# yack.net
KiCad netlist of a schematic drawn in EAGLE
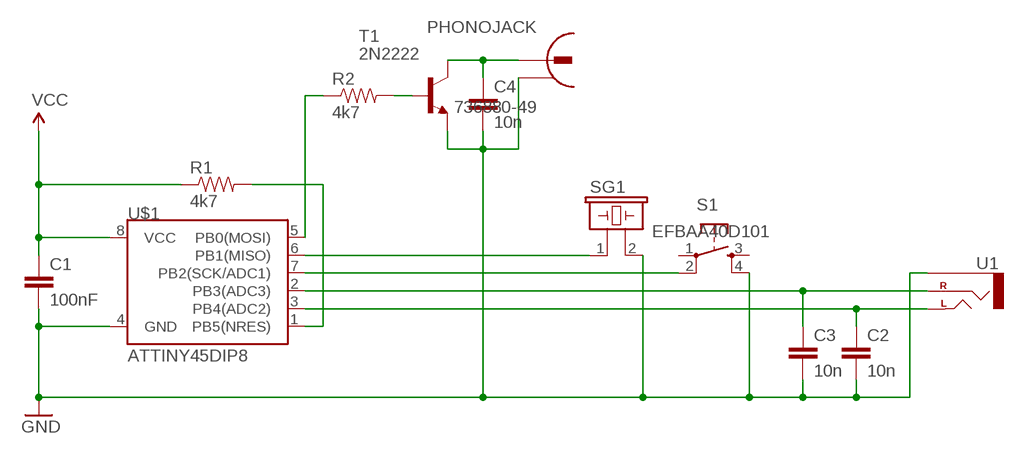
[diagram p0: schematic, sheet 1]

(export (version "E")
  (design (tool "Eeschema 10.0.6"))
  (components
    (comp (ref "C1")
      (value "100nF")
      (footprint "eagle-import:CAP-PTH-SMALL-KIT")
      (libsource (lib "eagle-import") (part "CAPKIT"))
    )
    (comp (ref "C2")
      (value "10n")
      (footprint "eagle-import:CAP-PTH-SMALL-KIT")
      (libsource (lib "eagle-import") (part "CAPKIT"))
    )
    (comp (ref "C3")
      (value "10n")
      (footprint "eagle-import:CAP-PTH-SMALL-KIT")
      (libsource (lib "eagle-import") (part "CAPKIT"))
    )
    (comp (ref "C4")
      (value "10n")
      (footprint "eagle-import:CAP-PTH-SMALL-KIT")
      (libsource (lib "eagle-import") (part "CAPKIT"))
    )
    (comp (ref "PHONOJACK")
      (value "736880-49")
      (footprint "eagle-import:736880-49")
      (libsource (lib "eagle-import") (part "736880-49"))
    )
    (comp (ref "R1")
      (value "4k7")
      (footprint "eagle-import:AXIAL-0.3-KIT")
      (libsource (lib "eagle-import") (part "RESISTORKIT"))
    )
    (comp (ref "R2")
      (value "4k7")
      (footprint "eagle-import:AXIAL-0.3-KIT")
      (libsource (lib "eagle-import") (part "RESISTORKIT"))
    )
    (comp (ref "S1")
      (value "TAC_SWITCHPTH")
      (footprint "eagle-import:TACTILE-PTH")
      (libsource (lib "eagle-import") (part "TAC_SWITCHPTH"))
    )
    (comp (ref "SG1")
      (value "EFBAA40D101")
      (footprint "eagle-import:EFBAA40D101")
      (libsource (lib "eagle-import") (part "EFB?AA40D101"))
    )
    (comp (ref "T1")
      (value "2N2222")
      (footprint "eagle-import:TO92-EBC-OVAL")
      (libsource (lib "eagle-import") (part "2N2222"))
    )
    (comp (ref "U$1")
      (value "ATTINY45DIP8")
      (footprint "eagle-import:DIP08")
      (libsource (lib "eagle-import") (part "ATTINY45DIP8"))
    )
    (comp (ref "U1")
      (value "AUDIO-JACKPTH")
      (footprint "eagle-import:AUDIO-JACK")
      (libsource (lib "eagle-import") (part "AUDIO-JACKPTH"))
    )
  )
  (nets
    (net (code "1") (name "GND") (class "Default")
      (node (ref "C1") (pin "2") (pinfunction "2_2") (pintype "passive"))
      (node (ref "C2") (pin "2") (pinfunction "2_2") (pintype "passive"))
      (node (ref "C3") (pin "2") (pinfunction "2_2") (pintype "passive"))
      (node (ref "C4") (pin "2") (pinfunction "2_2") (pintype "passive"))
      (node (ref "PHONOJACK") (pin "2") (pinfunction "2_2") (pintype "passive"))
      (node (ref "S1") (pin "4") (pinfunction "4_4") (pintype "passive"))
      (node (ref "SG1") (pin "2") (pinfunction "2_2") (pintype "passive"))
      (node (ref "T1") (pin "E") (pinfunction "E_E") (pintype "passive"))
      (node (ref "U$1") (pin "4") (pinfunction "GND_4") (pintype "bidirectional"))
      (node (ref "U1") (pin "SLEEVE") (pinfunction "SLEEVE_SLEEVE") (pintype "bidirectional"))
    )
    (net (code "2") (name "Net-(C4-Pad1)") (class "Default")
      (node (ref "C4") (pin "1") (pinfunction "1_1") (pintype "passive"))
      (node (ref "PHONOJACK") (pin "1") (pinfunction "1_1") (pintype "passive"))
      (node (ref "T1") (pin "C") (pinfunction "C_C") (pintype "passive"))
    )
    (net (code "3") (name "Net-(R1-2)") (class "Default")
      (node (ref "R1") (pin "P$2") (pinfunction "2_P$2") (pintype "passive"))
      (node (ref "U$1") (pin "1") (pinfunction "PB5(NRES)_1") (pintype "bidirectional"))
    )
    (net (code "4") (name "Net-(R2-1)") (class "Default")
      (node (ref "R2") (pin "P$1") (pinfunction "1_P$1") (pintype "passive"))
      (node (ref "U$1") (pin "5") (pinfunction "PB0(MOSI)_5") (pintype "bidirectional"))
    )
    (net (code "5") (name "Net-(R2-2)") (class "Default")
      (node (ref "R2") (pin "P$2") (pinfunction "2_P$2") (pintype "passive"))
      (node (ref "T1") (pin "B") (pinfunction "B_B") (pintype "passive"))
    )
    (net (code "6") (name "Net-(U$1-PB1(MISO))") (class "Default")
      (node (ref "SG1") (pin "1") (pinfunction "1_1") (pintype "passive"))
      (node (ref "U$1") (pin "6") (pinfunction "PB1(MISO)_6") (pintype "bidirectional"))
    )
    (net (code "7") (name "Net-(U$1-PB2(SCK{slash}ADC1))") (class "Default")
      (node (ref "S1") (pin "2") (pinfunction "2_2") (pintype "passive"))
      (node (ref "U$1") (pin "7") (pinfunction "PB2(SCK/ADC1)_7") (pintype "bidirectional"))
    )
    (net (code "8") (name "Net-(U$1-PB3(ADC3))") (class "Default")
      (node (ref "C3") (pin "1") (pinfunction "1_1") (pintype "passive"))
      (node (ref "U$1") (pin "2") (pinfunction "PB3(ADC3)_2") (pintype "bidirectional"))
      (node (ref "U1") (pin "RING") (pinfunction "RIGHT_RING") (pintype "bidirectional"))
    )
    (net (code "9") (name "Net-(U$1-PB4(ADC2))") (class "Default")
      (node (ref "C2") (pin "1") (pinfunction "1_1") (pintype "passive"))
      (node (ref "U$1") (pin "3") (pinfunction "PB4(ADC2)_3") (pintype "bidirectional"))
      (node (ref "U1") (pin "TIP") (pinfunction "LEFT_TIP") (pintype "bidirectional"))
    )
    (net (code "10") (name "VCC") (class "Default")
      (node (ref "C1") (pin "1") (pinfunction "1_1") (pintype "passive"))
      (node (ref "R1") (pin "P$1") (pinfunction "1_P$1") (pintype "passive"))
      (node (ref "U$1") (pin "8") (pinfunction "VCC_8") (pintype "bidirectional"))
    )
    (net (code "11") (name "unconnected-(PHONOJACK-2-Pad2@2)") (class "Default")
      (node (ref "PHONOJACK") (pin "2@2") (pinfunction "2_2@2") (pintype "passive"))
    )
    (net (code "12") (name "unconnected-(S1-Pad1)") (class "Default")
      (node (ref "S1") (pin "1") (pinfunction "1_1") (pintype "passive"))
    )
    (net (code "13") (name "unconnected-(S1-Pad3)") (class "Default")
      (node (ref "S1") (pin "3") (pinfunction "3_3") (pintype "passive"))
    )
  )
)
